# design.net
KiCad netlist of a schematic drawn in EasyEDA Pro
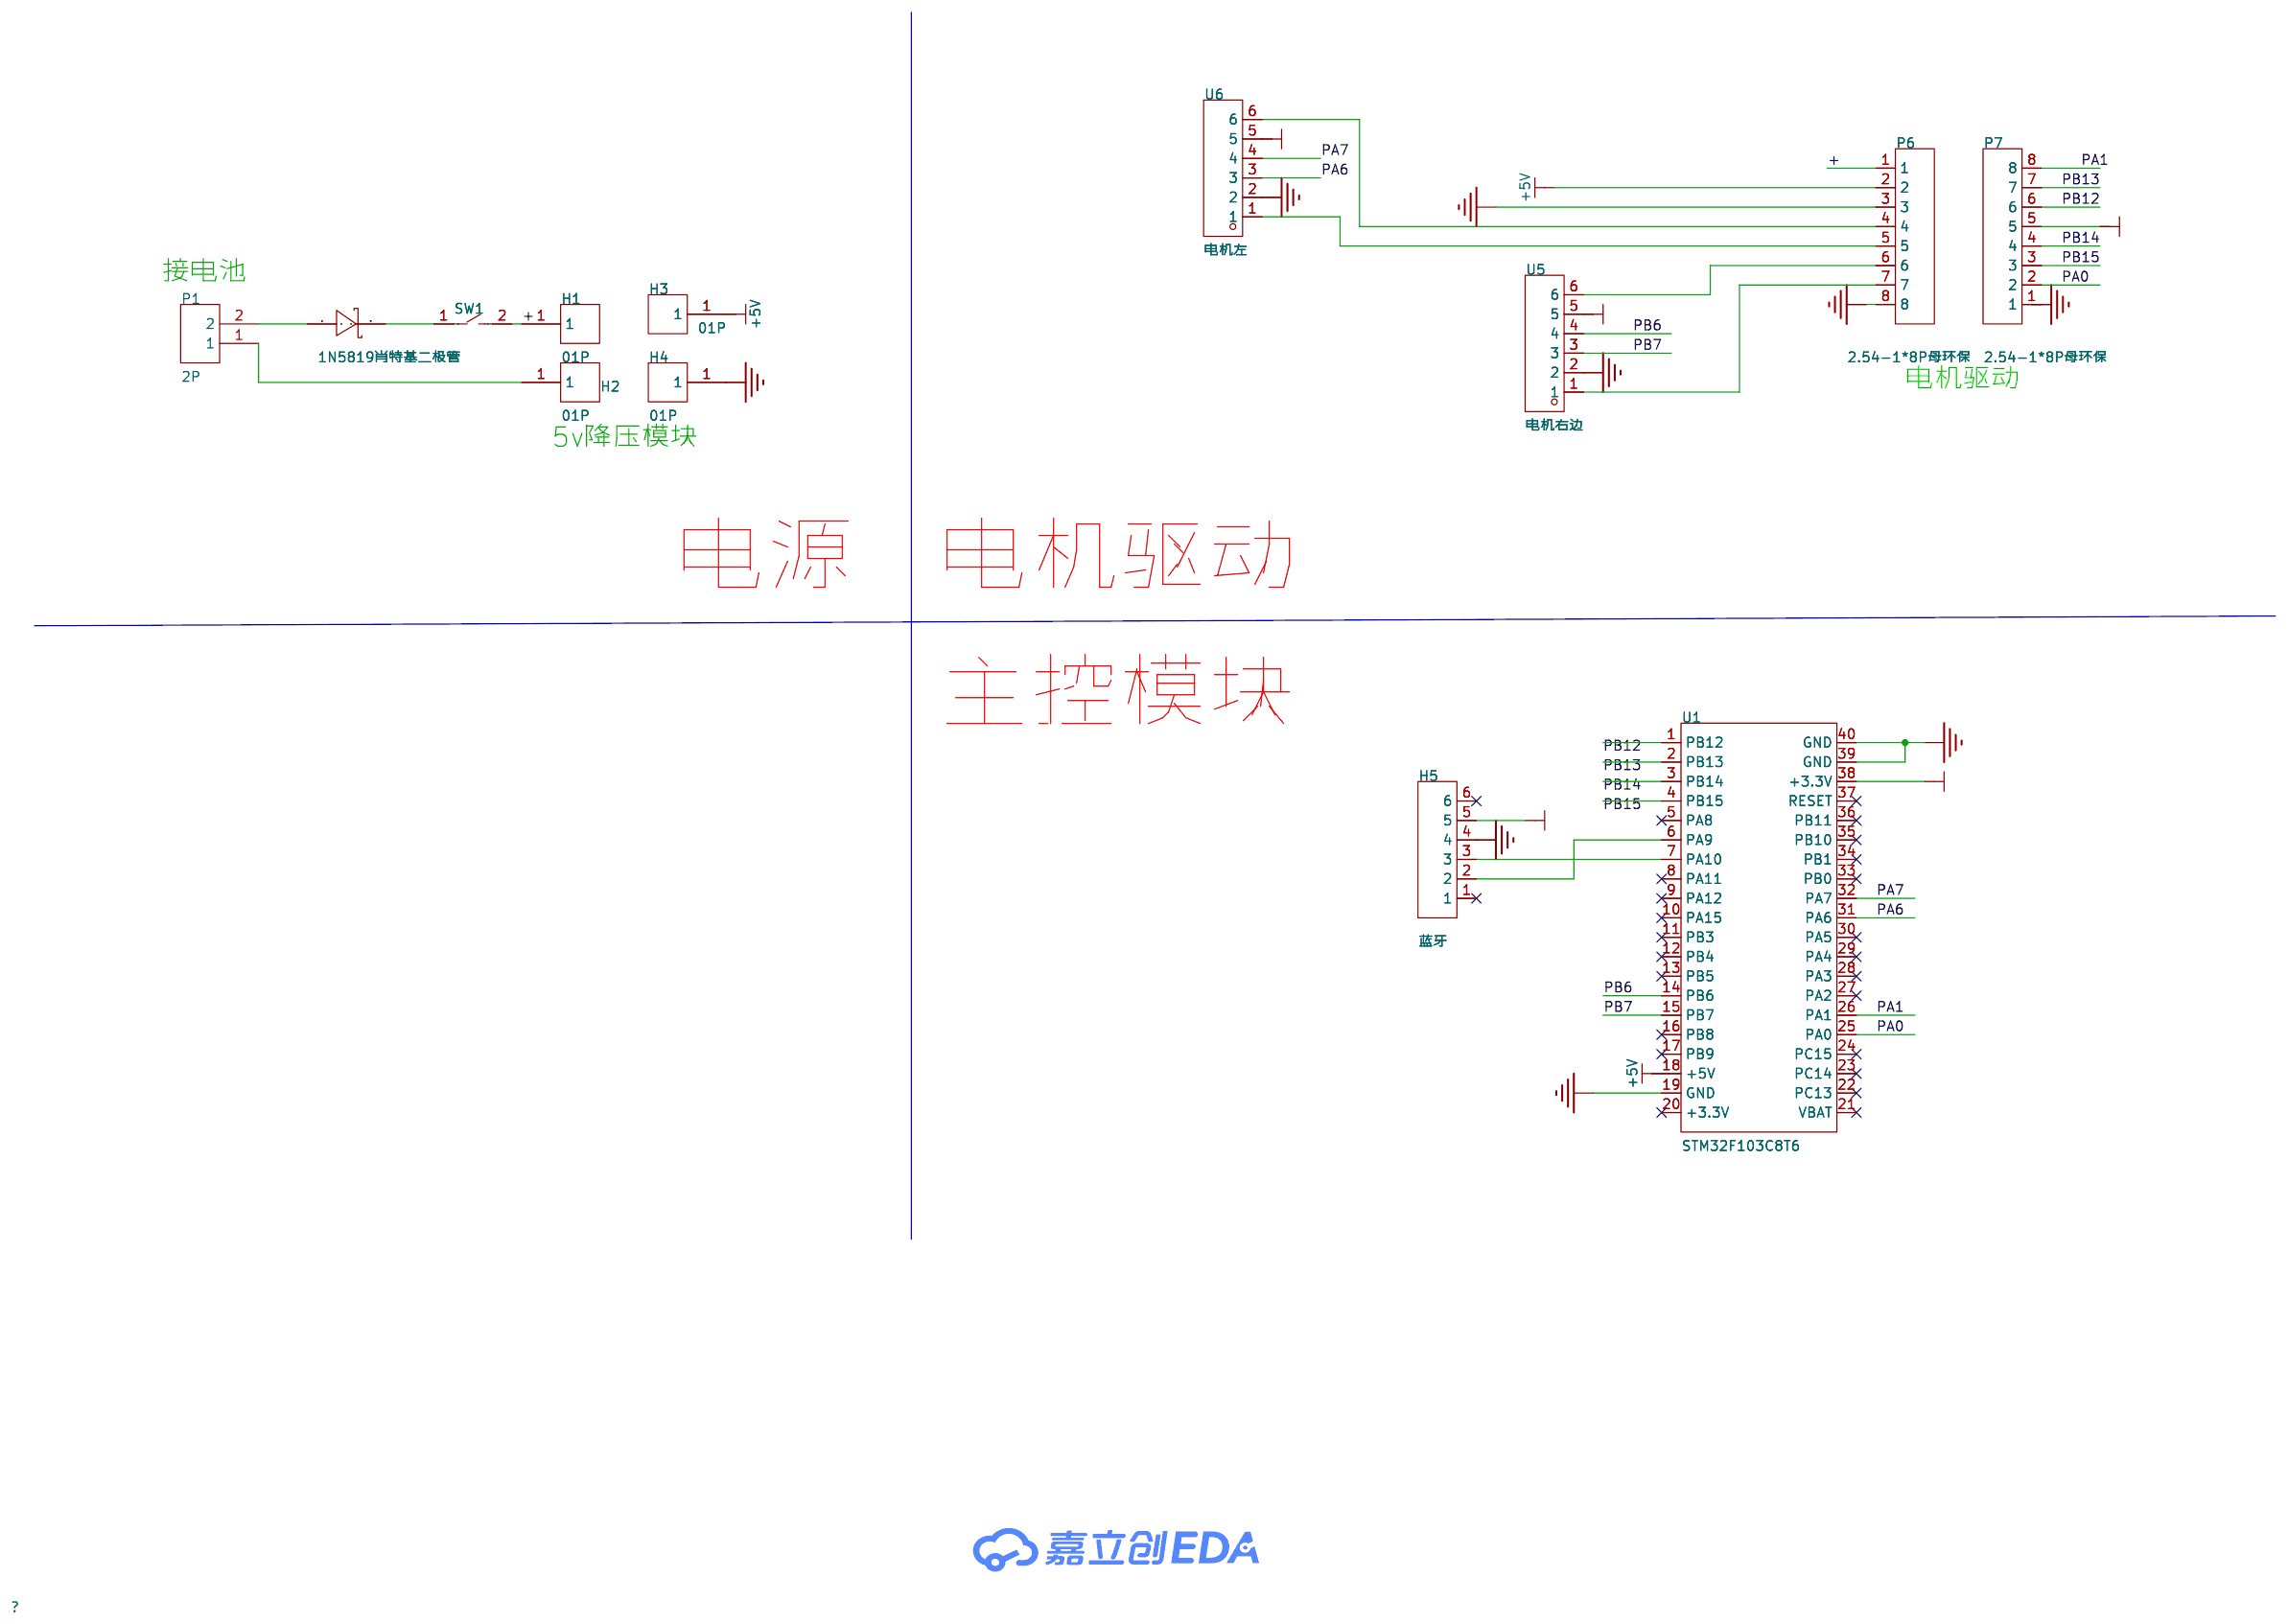
[diagram p0: schematic sheet]

(export (version "E")
  (design (tool "Eeschema 10.0.6"))
  (components
    (comp (ref "D1")
      (value "1N5819肖特基二极管")
      (footprint "easyedapro:DO-41_BD2.4-L4.7-P8.70-D0.9-FD")
      (description "正向压降(Vf):550mV@1A;直流反向耐压(Vr):40V;整流电流:1A;")
      (fields (field (name "Manufacturer") "ST(意法半导体)"))
      (libsource (lib "easyedapro") (part "1N5819"))
    )
    (comp (ref "H1")
      (value "01P")
      (footprint "easyedapro:HDR-TH_1P-P2.54-V-M")
      (fields (field (name "Manufacturer") "XFCN(兴飞)"))
      (libsource (lib "easyedapro") (part "PZ254V-11-01P"))
    )
    (comp (ref "H2")
      (value "01P")
      (footprint "easyedapro:HDR-TH_1P-P2.54-V-M")
      (fields (field (name "Manufacturer") "XFCN(兴飞)"))
      (libsource (lib "easyedapro") (part "PZ254V-11-01P"))
    )
    (comp (ref "H3")
      (value "01P")
      (footprint "easyedapro:HDR-TH_1P-P2.54-V-M")
      (fields (field (name "Manufacturer") "XFCN(兴飞)"))
      (libsource (lib "easyedapro") (part "PZ254V-11-01P"))
    )
    (comp (ref "H4")
      (value "01P")
      (footprint "easyedapro:HDR-TH_1P-P2.54-V-M")
      (fields (field (name "Manufacturer") "XFCN(兴飞)"))
      (libsource (lib "easyedapro") (part "PZ254V-11-01P"))
    )
    (comp (ref "H5")
      (value "蓝牙")
      (footprint "easyedapro:HDR-TH_6P-P2.54-H-F-W10.2")
      (fields (field (name "Manufacturer") "SHOU HAN(首韩)"))
      (libsource (lib "easyedapro") (part "2.54-1X6P WZPM"))
    )
    (comp (ref "P1")
      (value "2P")
      (footprint "easyedapro:CONN-TH_2P-P5.00_WJ500V-5.08-2P")
      (fields (field (name "Manufacturer") "KANGNEX(康奈克斯电气)"))
      (libsource (lib "easyedapro") (part "WJ500V-5.08-2P-14-00A"))
    )
    (comp (ref "P6")
      (value "2.54-1*8P母环保")
      (footprint "easyedapro:HDR-TH_8P-P2.54-V-F_2")
      (fields (field (name "Manufacturer") "BOOMELE(博穆精密)"))
      (libsource (lib "easyedapro") (part "Header-Female-2.54_1x8"))
    )
    (comp (ref "P7")
      (value "2.54-1*8P母环保")
      (footprint "easyedapro:HDR-TH_8P-P2.54-V-F_2")
      (fields (field (name "Manufacturer") "BOOMELE(博穆精密)"))
      (libsource (lib "easyedapro") (part "Header-Female-2.54_1x8"))
    )
    (comp (ref "SW1")
      (value "HX KCD11-2P-R")
      (footprint "easyedapro:SW-TH_2P-L15.0-W10.5-P5.00_KCD11-2P-R")
      (description "带灯:无;引脚样式:焊片;额定电流:3A;额定电压(AC):250V;电路结构:单刀单掷;工作寿命:1万次;")
      (fields (field (name "Manufacturer") "hanxia(韩下)"))
      (libsource (lib "easyedapro") (part "HX KCD11-2P-R"))
    )
    (comp (ref "U1")
      (value "STM32F103C8T6")
      (footprint "easyedapro:CONN-TH_L53.3-W22.9_STM32F103C8T6-CARD")
      (description "搭载Contex M3内核,程序存储容量64KB,RAM总容量20KB,最高72MHz主频,提供高效的计算能力和稳定的运行环境。")
      (fields (field (name "Manufacturer") "立创开发板"))
      (libsource (lib "easyedapro") (part "LCKFB-DKX-STM32F103C8T6"))
    )
    (comp (ref "U5")
      (value "电机右边")
      (footprint "easyedapro:CONN-TH_6P-P2.50_ZX-XH2.54-6PWZ")
      (fields (field (name "Manufacturer") "Megastar(兆星)"))
      (libsource (lib "easyedapro") (part "ZX-XH2.54-6PWZ"))
    )
    (comp (ref "U6")
      (value "电机左")
      (footprint "easyedapro:CONN-TH_6P-P2.50_ZX-XH2.54-6PWZ")
      (fields (field (name "Manufacturer") "Megastar(兆星)"))
      (libsource (lib "easyedapro") (part "ZX-XH2.54-6PWZ"))
    )
  )
  (nets
    (net (code "1") (name "+5V") (class "Default")
      (node (ref "H3") (pin "1") (pinfunction "1_1") (pintype "unspecified"))
      (node (ref "P6") (pin "2") (pinfunction "2_2") (pintype "unspecified"))
      (node (ref "U1") (pin "18") (pinfunction "+5V_18") (pintype "unspecified"))
    )
    (net (code "2") (name "/+") (class "Default")
      (node (ref "H1") (pin "1") (pinfunction "1_1") (pintype "unspecified"))
      (node (ref "P6") (pin "1") (pinfunction "1_1") (pintype "unspecified"))
      (node (ref "SW1") (pin "2") (pinfunction "2_2") (pintype "unspecified"))
    )
    (net (code "3") (name "/PA0") (class "Default")
      (node (ref "P7") (pin "2") (pinfunction "2_2") (pintype "unspecified"))
      (node (ref "U1") (pin "25") (pinfunction "PA0_25") (pintype "unspecified"))
    )
    (net (code "4") (name "/PA1") (class "Default")
      (node (ref "P7") (pin "8") (pinfunction "8_8") (pintype "unspecified"))
      (node (ref "U1") (pin "26") (pinfunction "PA1_26") (pintype "unspecified"))
    )
    (net (code "5") (name "/PA6") (class "Default")
      (node (ref "U1") (pin "31") (pinfunction "PA6_31") (pintype "unspecified"))
      (node (ref "U6") (pin "3") (pinfunction "3_3") (pintype "unspecified"))
    )
    (net (code "6") (name "/PA7") (class "Default")
      (node (ref "U1") (pin "32") (pinfunction "PA7_32") (pintype "unspecified"))
      (node (ref "U6") (pin "4") (pinfunction "4_4") (pintype "unspecified"))
    )
    (net (code "7") (name "/PB6") (class "Default")
      (node (ref "U1") (pin "14") (pinfunction "PB6_14") (pintype "unspecified"))
      (node (ref "U5") (pin "4") (pinfunction "4_4") (pintype "unspecified"))
    )
    (net (code "8") (name "/PB7") (class "Default")
      (node (ref "U1") (pin "15") (pinfunction "PB7_15") (pintype "unspecified"))
      (node (ref "U5") (pin "3") (pinfunction "3_3") (pintype "unspecified"))
    )
    (net (code "9") (name "/PB12") (class "Default")
      (node (ref "P7") (pin "6") (pinfunction "6_6") (pintype "unspecified"))
      (node (ref "U1") (pin "1") (pinfunction "PB12_1") (pintype "unspecified"))
    )
    (net (code "10") (name "/PB13") (class "Default")
      (node (ref "P7") (pin "7") (pinfunction "7_7") (pintype "unspecified"))
      (node (ref "U1") (pin "2") (pinfunction "PB13_2") (pintype "unspecified"))
    )
    (net (code "11") (name "/PB14") (class "Default")
      (node (ref "P7") (pin "4") (pinfunction "4_4") (pintype "unspecified"))
      (node (ref "U1") (pin "3") (pinfunction "PB14_3") (pintype "unspecified"))
    )
    (net (code "12") (name "/PB15") (class "Default")
      (node (ref "P7") (pin "3") (pinfunction "3_3") (pintype "unspecified"))
      (node (ref "U1") (pin "4") (pinfunction "PB15_4") (pintype "unspecified"))
    )
    (net (code "13") (name "3.3V") (class "Default")
      (node (ref "H5") (pin "5") (pinfunction "5_5") (pintype "unspecified"))
      (node (ref "P7") (pin "5") (pinfunction "5_5") (pintype "unspecified"))
      (node (ref "U1") (pin "38") (pinfunction "+3.3V_38") (pintype "unspecified"))
      (node (ref "U5") (pin "5") (pinfunction "5_5") (pintype "unspecified"))
      (node (ref "U6") (pin "5") (pinfunction "5_5") (pintype "unspecified"))
    )
    (net (code "14") (name "GND") (class "Default")
      (node (ref "H4") (pin "1") (pinfunction "1_1") (pintype "unspecified"))
      (node (ref "H5") (pin "4") (pinfunction "4_4") (pintype "unspecified"))
      (node (ref "P6") (pin "3") (pinfunction "3_3") (pintype "unspecified"))
      (node (ref "P6") (pin "8") (pinfunction "8_8") (pintype "unspecified"))
      (node (ref "P7") (pin "1") (pinfunction "1_1") (pintype "unspecified"))
      (node (ref "U1") (pin "19") (pinfunction "GND_19") (pintype "unspecified"))
      (node (ref "U1") (pin "39") (pinfunction "GND_39") (pintype "unspecified"))
      (node (ref "U1") (pin "40") (pinfunction "GND_40") (pintype "unspecified"))
      (node (ref "U5") (pin "2") (pinfunction "2_2") (pintype "unspecified"))
      (node (ref "U6") (pin "2") (pinfunction "2_2") (pintype "unspecified"))
    )
    (net (code "15") (name "Net-(D1-A)") (class "Default")
      (node (ref "D1") (pin "1") (pinfunction "A_1") (pintype "unspecified"))
      (node (ref "P1") (pin "2") (pinfunction "2_2") (pintype "unspecified"))
    )
    (net (code "16") (name "Net-(D1-K)") (class "Default")
      (node (ref "D1") (pin "2") (pinfunction "K_2") (pintype "unspecified"))
      (node (ref "SW1") (pin "1") (pinfunction "1_1") (pintype "unspecified"))
    )
    (net (code "17") (name "Net-(H2-Pad1)") (class "Default")
      (node (ref "H2") (pin "1") (pinfunction "1_1") (pintype "unspecified"))
      (node (ref "P1") (pin "1") (pinfunction "1_1") (pintype "unspecified"))
    )
    (net (code "18") (name "Net-(P6-Pad4)") (class "Default")
      (node (ref "P6") (pin "4") (pinfunction "4_4") (pintype "unspecified"))
      (node (ref "U6") (pin "6") (pinfunction "6_6") (pintype "unspecified"))
    )
    (net (code "19") (name "Net-(P6-Pad5)") (class "Default")
      (node (ref "P6") (pin "5") (pinfunction "5_5") (pintype "unspecified"))
      (node (ref "U6") (pin "1") (pinfunction "1_1") (pintype "unspecified"))
    )
    (net (code "20") (name "Net-(P6-Pad6)") (class "Default")
      (node (ref "P6") (pin "6") (pinfunction "6_6") (pintype "unspecified"))
      (node (ref "U5") (pin "6") (pinfunction "6_6") (pintype "unspecified"))
    )
    (net (code "21") (name "Net-(P6-Pad7)") (class "Default")
      (node (ref "P6") (pin "7") (pinfunction "7_7") (pintype "unspecified"))
      (node (ref "U5") (pin "1") (pinfunction "1_1") (pintype "unspecified"))
    )
    (net (code "22") (name "Net-(U1-PA9)") (class "Default")
      (node (ref "H5") (pin "2") (pinfunction "2_2") (pintype "unspecified"))
      (node (ref "U1") (pin "6") (pinfunction "PA9_6") (pintype "unspecified"))
    )
    (net (code "23") (name "Net-(U1-PA10)") (class "Default")
      (node (ref "H5") (pin "3") (pinfunction "3_3") (pintype "unspecified"))
      (node (ref "U1") (pin "7") (pinfunction "PA10_7") (pintype "unspecified"))
    )
    (net (code "24") (name "unconnected-(H5-Pad1)") (class "Default")
      (node (ref "H5") (pin "1") (pinfunction "1_1") (pintype "unspecified+no_connect"))
    )
    (net (code "25") (name "unconnected-(H5-Pad6)") (class "Default")
      (node (ref "H5") (pin "6") (pinfunction "6_6") (pintype "unspecified+no_connect"))
    )
    (net (code "26") (name "unconnected-(U1-+3.3V-Pad20)") (class "Default")
      (node (ref "U1") (pin "20") (pinfunction "+3.3V_20") (pintype "unspecified+no_connect"))
    )
    (net (code "27") (name "unconnected-(U1-PA2-Pad27)") (class "Default")
      (node (ref "U1") (pin "27") (pinfunction "PA2_27") (pintype "unspecified+no_connect"))
    )
    (net (code "28") (name "unconnected-(U1-PA3-Pad28)") (class "Default")
      (node (ref "U1") (pin "28") (pinfunction "PA3_28") (pintype "unspecified+no_connect"))
    )
    (net (code "29") (name "unconnected-(U1-PA4-Pad29)") (class "Default")
      (node (ref "U1") (pin "29") (pinfunction "PA4_29") (pintype "unspecified+no_connect"))
    )
    (net (code "30") (name "unconnected-(U1-PA5-Pad30)") (class "Default")
      (node (ref "U1") (pin "30") (pinfunction "PA5_30") (pintype "unspecified+no_connect"))
    )
    (net (code "31") (name "unconnected-(U1-PA8-Pad5)") (class "Default")
      (node (ref "U1") (pin "5") (pinfunction "PA8_5") (pintype "unspecified+no_connect"))
    )
    (net (code "32") (name "unconnected-(U1-PA11-Pad8)") (class "Default")
      (node (ref "U1") (pin "8") (pinfunction "PA11_8") (pintype "unspecified+no_connect"))
    )
    (net (code "33") (name "unconnected-(U1-PA12-Pad9)") (class "Default")
      (node (ref "U1") (pin "9") (pinfunction "PA12_9") (pintype "unspecified+no_connect"))
    )
    (net (code "34") (name "unconnected-(U1-PA15-Pad10)") (class "Default")
      (node (ref "U1") (pin "10") (pinfunction "PA15_10") (pintype "unspecified+no_connect"))
    )
    (net (code "35") (name "unconnected-(U1-PB0-Pad33)") (class "Default")
      (node (ref "U1") (pin "33") (pinfunction "PB0_33") (pintype "unspecified+no_connect"))
    )
    (net (code "36") (name "unconnected-(U1-PB1-Pad34)") (class "Default")
      (node (ref "U1") (pin "34") (pinfunction "PB1_34") (pintype "unspecified+no_connect"))
    )
    (net (code "37") (name "unconnected-(U1-PB3-Pad11)") (class "Default")
      (node (ref "U1") (pin "11") (pinfunction "PB3_11") (pintype "unspecified+no_connect"))
    )
    (net (code "38") (name "unconnected-(U1-PB4-Pad12)") (class "Default")
      (node (ref "U1") (pin "12") (pinfunction "PB4_12") (pintype "unspecified+no_connect"))
    )
    (net (code "39") (name "unconnected-(U1-PB5-Pad13)") (class "Default")
      (node (ref "U1") (pin "13") (pinfunction "PB5_13") (pintype "unspecified+no_connect"))
    )
    (net (code "40") (name "unconnected-(U1-PB8-Pad16)") (class "Default")
      (node (ref "U1") (pin "16") (pinfunction "PB8_16") (pintype "unspecified+no_connect"))
    )
    (net (code "41") (name "unconnected-(U1-PB9-Pad17)") (class "Default")
      (node (ref "U1") (pin "17") (pinfunction "PB9_17") (pintype "unspecified+no_connect"))
    )
    (net (code "42") (name "unconnected-(U1-PB10-Pad35)") (class "Default")
      (node (ref "U1") (pin "35") (pinfunction "PB10_35") (pintype "unspecified+no_connect"))
    )
    (net (code "43") (name "unconnected-(U1-PB11-Pad36)") (class "Default")
      (node (ref "U1") (pin "36") (pinfunction "PB11_36") (pintype "unspecified+no_connect"))
    )
    (net (code "44") (name "unconnected-(U1-PC13-Pad22)") (class "Default")
      (node (ref "U1") (pin "22") (pinfunction "PC13_22") (pintype "unspecified+no_connect"))
    )
    (net (code "45") (name "unconnected-(U1-PC14-Pad23)") (class "Default")
      (node (ref "U1") (pin "23") (pinfunction "PC14_23") (pintype "unspecified+no_connect"))
    )
    (net (code "46") (name "unconnected-(U1-PC15-Pad24)") (class "Default")
      (node (ref "U1") (pin "24") (pinfunction "PC15_24") (pintype "unspecified+no_connect"))
    )
    (net (code "47") (name "unconnected-(U1-RESET-Pad37)") (class "Default")
      (node (ref "U1") (pin "37") (pinfunction "RESET_37") (pintype "unspecified+no_connect"))
    )
    (net (code "48") (name "unconnected-(U1-VBAT-Pad21)") (class "Default")
      (node (ref "U1") (pin "21") (pinfunction "VBAT_21") (pintype "unspecified+no_connect"))
    )
  )
)
